# Connectors.net
KiCad netlist of a schematic drawn in Altium Designer
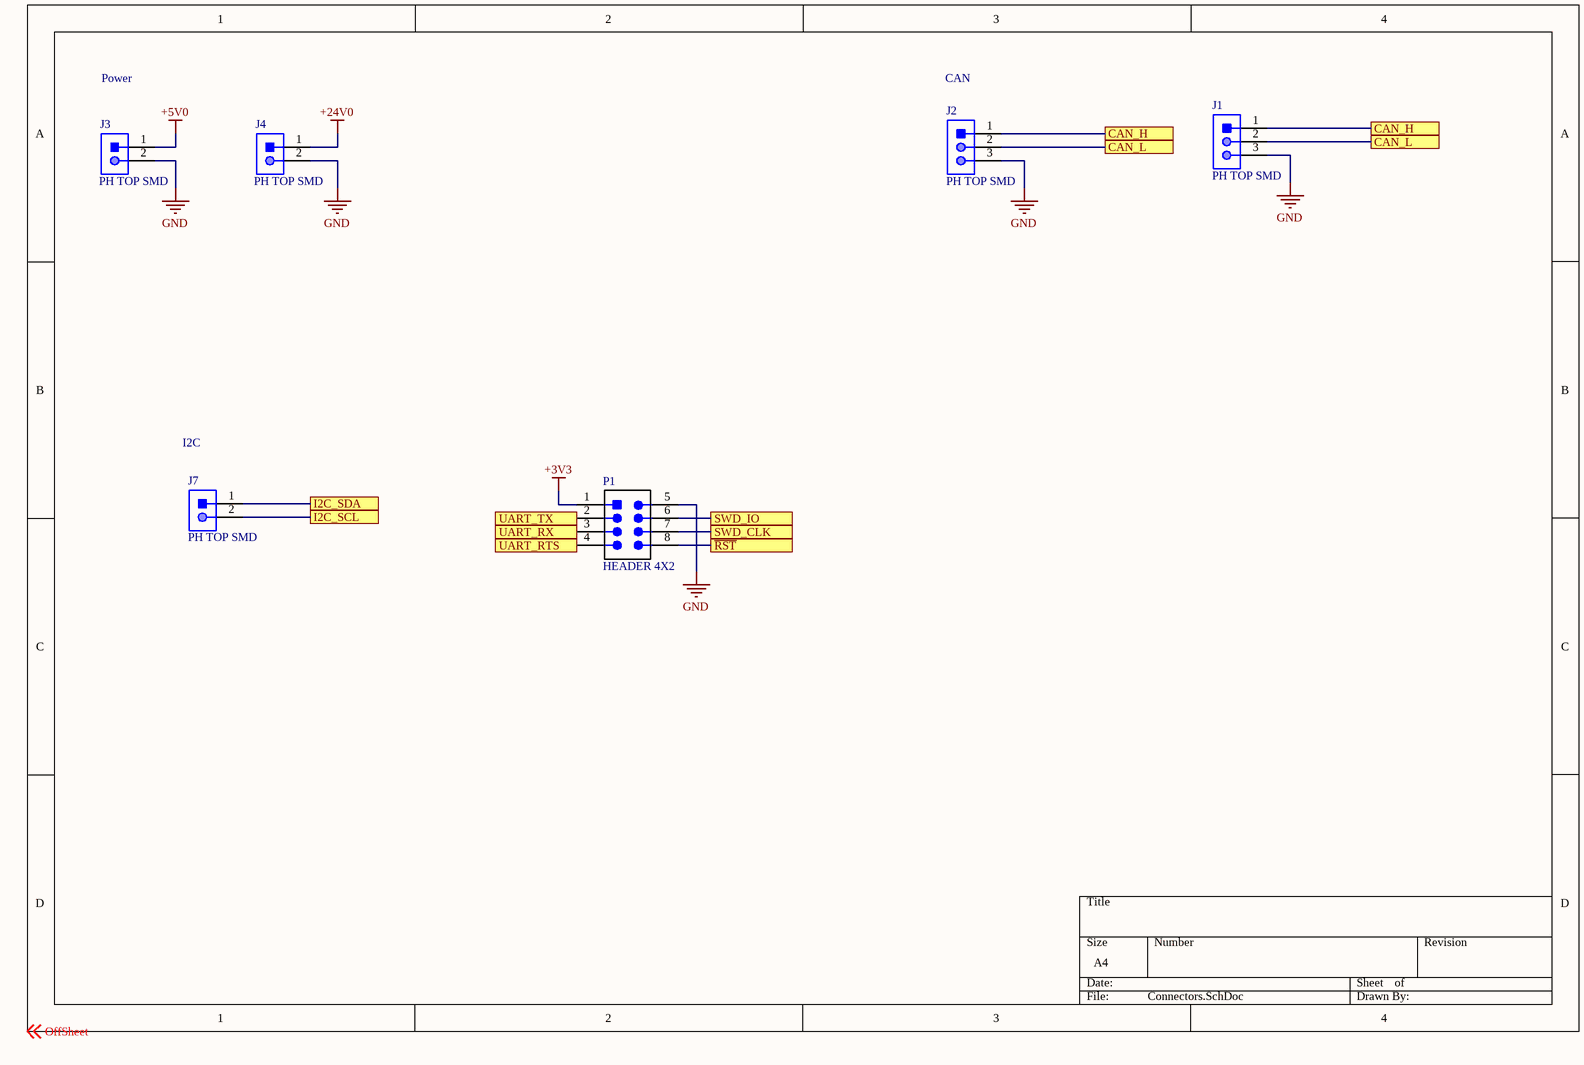
[diagram p0: Connectors.SchDoc]

(export (version "E")
  (design (tool "Eeschema 10.0.6"))
  (components
    (comp (ref "J1")
      (value "PH TOP SMD")
      (footprint "JST-B3B-SM4-TB")
      (description "CONN HEADER PH TOP 3POS 2MM SMD")
      (fields (field (name "MANUFACTURER") "JST") (field (name "PART NUMBER") "B3B-PH-SM4-TB"))
      (libsource (lib "UWRT_Schematic_Library_2019") (part "CON_3M_PH_TOP_SMT"))
    )
    (comp (ref "J2")
      (value "PH TOP SMD")
      (footprint "JST-B3B-SM4-TB")
      (description "CONN HEADER PH TOP 3POS 2MM SMD")
      (fields (field (name "MANUFACTURER") "JST") (field (name "PART NUMBER") "B3B-PH-SM4-TB"))
      (libsource (lib "UWRT_Schematic_Library_2019") (part "CON_3M_PH_TOP_SMT"))
    )
    (comp (ref "J3")
      (value "PH TOP SMD")
      (footprint "JST-B2B-SM4-TB")
      (description "CONN HEADER PH TOP 2POS 2MM SMD")
      (fields (field (name "MANUFACTURER") "JST") (field (name "PART NUMBER") "B2B-PH-SM4-TB"))
      (libsource (lib "UWRT_Schematic_Library_2019") (part "CON_2M_PH_TOP_SMT"))
    )
    (comp (ref "J4")
      (value "PH TOP SMD")
      (footprint "JST-B2B-SM4-TB")
      (description "CONN HEADER PH TOP 2POS 2MM SMD")
      (fields (field (name "MANUFACTURER") "JST") (field (name "PART NUMBER") "B2B-PH-SM4-TB"))
      (libsource (lib "UWRT_Schematic_Library_2019") (part "CON_2M_PH_TOP_SMT"))
    )
    (comp (ref "J7")
      (value "PH TOP SMD")
      (footprint "JST-B2B-SM4-TB")
      (description "CONN HEADER PH TOP 2POS 2MM SMD")
      (fields (field (name "MANUFACTURER") "JST") (field (name "PART NUMBER") "B2B-PH-SM4-TB"))
      (libsource (lib "UWRT_Schematic_Library_2019") (part "CON_2M_PH_TOP_SMT"))
    )
    (comp (ref "P1")
      (value "HEADER 4X2")
      (footprint "UWRT_Footprint_Library_2019:HEADER_2X4")
      (description "Header, 4-Pin Dual row")
      (fields (field (name "PUBLISHER") "Altium Limited"))
      (libsource (lib "UWRT_Schematic_Library_2019") (part "HEADER 4X2"))
    )
  )
  (nets
    (net (code "1") (name "+3V3") (class "Default")
      (node (ref "P1") (pin "1") (pinfunction "VCC_1") (pintype "passive"))
    )
    (net (code "2") (name "+5V0") (class "Default")
      (node (ref "J3") (pin "1") (pinfunction "1_1") (pintype "passive"))
    )
    (net (code "3") (name "+24V0") (class "Default")
      (node (ref "J4") (pin "1") (pinfunction "1_1") (pintype "passive"))
    )
    (net (code "4") (name "/CAN_H") (class "Default")
      (node (ref "J1") (pin "1") (pinfunction "1_1") (pintype "passive"))
      (node (ref "J2") (pin "1") (pinfunction "1_1") (pintype "passive"))
    )
    (net (code "5") (name "/CAN_L") (class "Default")
      (node (ref "J1") (pin "2") (pinfunction "2_2") (pintype "passive"))
      (node (ref "J2") (pin "2") (pinfunction "2_2") (pintype "passive"))
    )
    (net (code "6") (name "/I2C_SCL") (class "Default")
      (node (ref "J7") (pin "2") (pinfunction "2_2") (pintype "passive"))
    )
    (net (code "7") (name "/I2C_SDA") (class "Default")
      (node (ref "J7") (pin "1") (pinfunction "1_1") (pintype "passive"))
    )
    (net (code "8") (name "/SWD_CLK") (class "Default")
      (node (ref "P1") (pin "7") (pinfunction "3_7") (pintype "passive"))
    )
    (net (code "9") (name "/SWD_IO") (class "Default")
      (node (ref "P1") (pin "6") (pinfunction "2_6") (pintype "passive"))
    )
    (net (code "10") (name "/UART_RTS") (class "Default")
      (node (ref "P1") (pin "4") (pinfunction "4_4") (pintype "passive"))
    )
    (net (code "11") (name "/UART_RX") (class "Default")
      (node (ref "P1") (pin "3") (pinfunction "3_3") (pintype "passive"))
    )
    (net (code "12") (name "/UART_TX") (class "Default")
      (node (ref "P1") (pin "2") (pinfunction "2_2") (pintype "passive"))
    )
    (net (code "13") (name "/~{RST}") (class "Default")
      (node (ref "P1") (pin "8") (pinfunction "4_8") (pintype "passive"))
    )
    (net (code "14") (name "GND") (class "Default")
      (node (ref "J1") (pin "3") (pinfunction "3_3") (pintype "passive"))
      (node (ref "J2") (pin "3") (pinfunction "3_3") (pintype "passive"))
      (node (ref "J3") (pin "2") (pinfunction "2_2") (pintype "passive"))
      (node (ref "J4") (pin "2") (pinfunction "2_2") (pintype "passive"))
      (node (ref "P1") (pin "5") (pinfunction "GND_5") (pintype "passive"))
    )
  )
)
